# ecube_EIB_HS64_2xOmnetics_r1_0_30mm.net
KiCad netlist of a schematic drawn in EAGLE
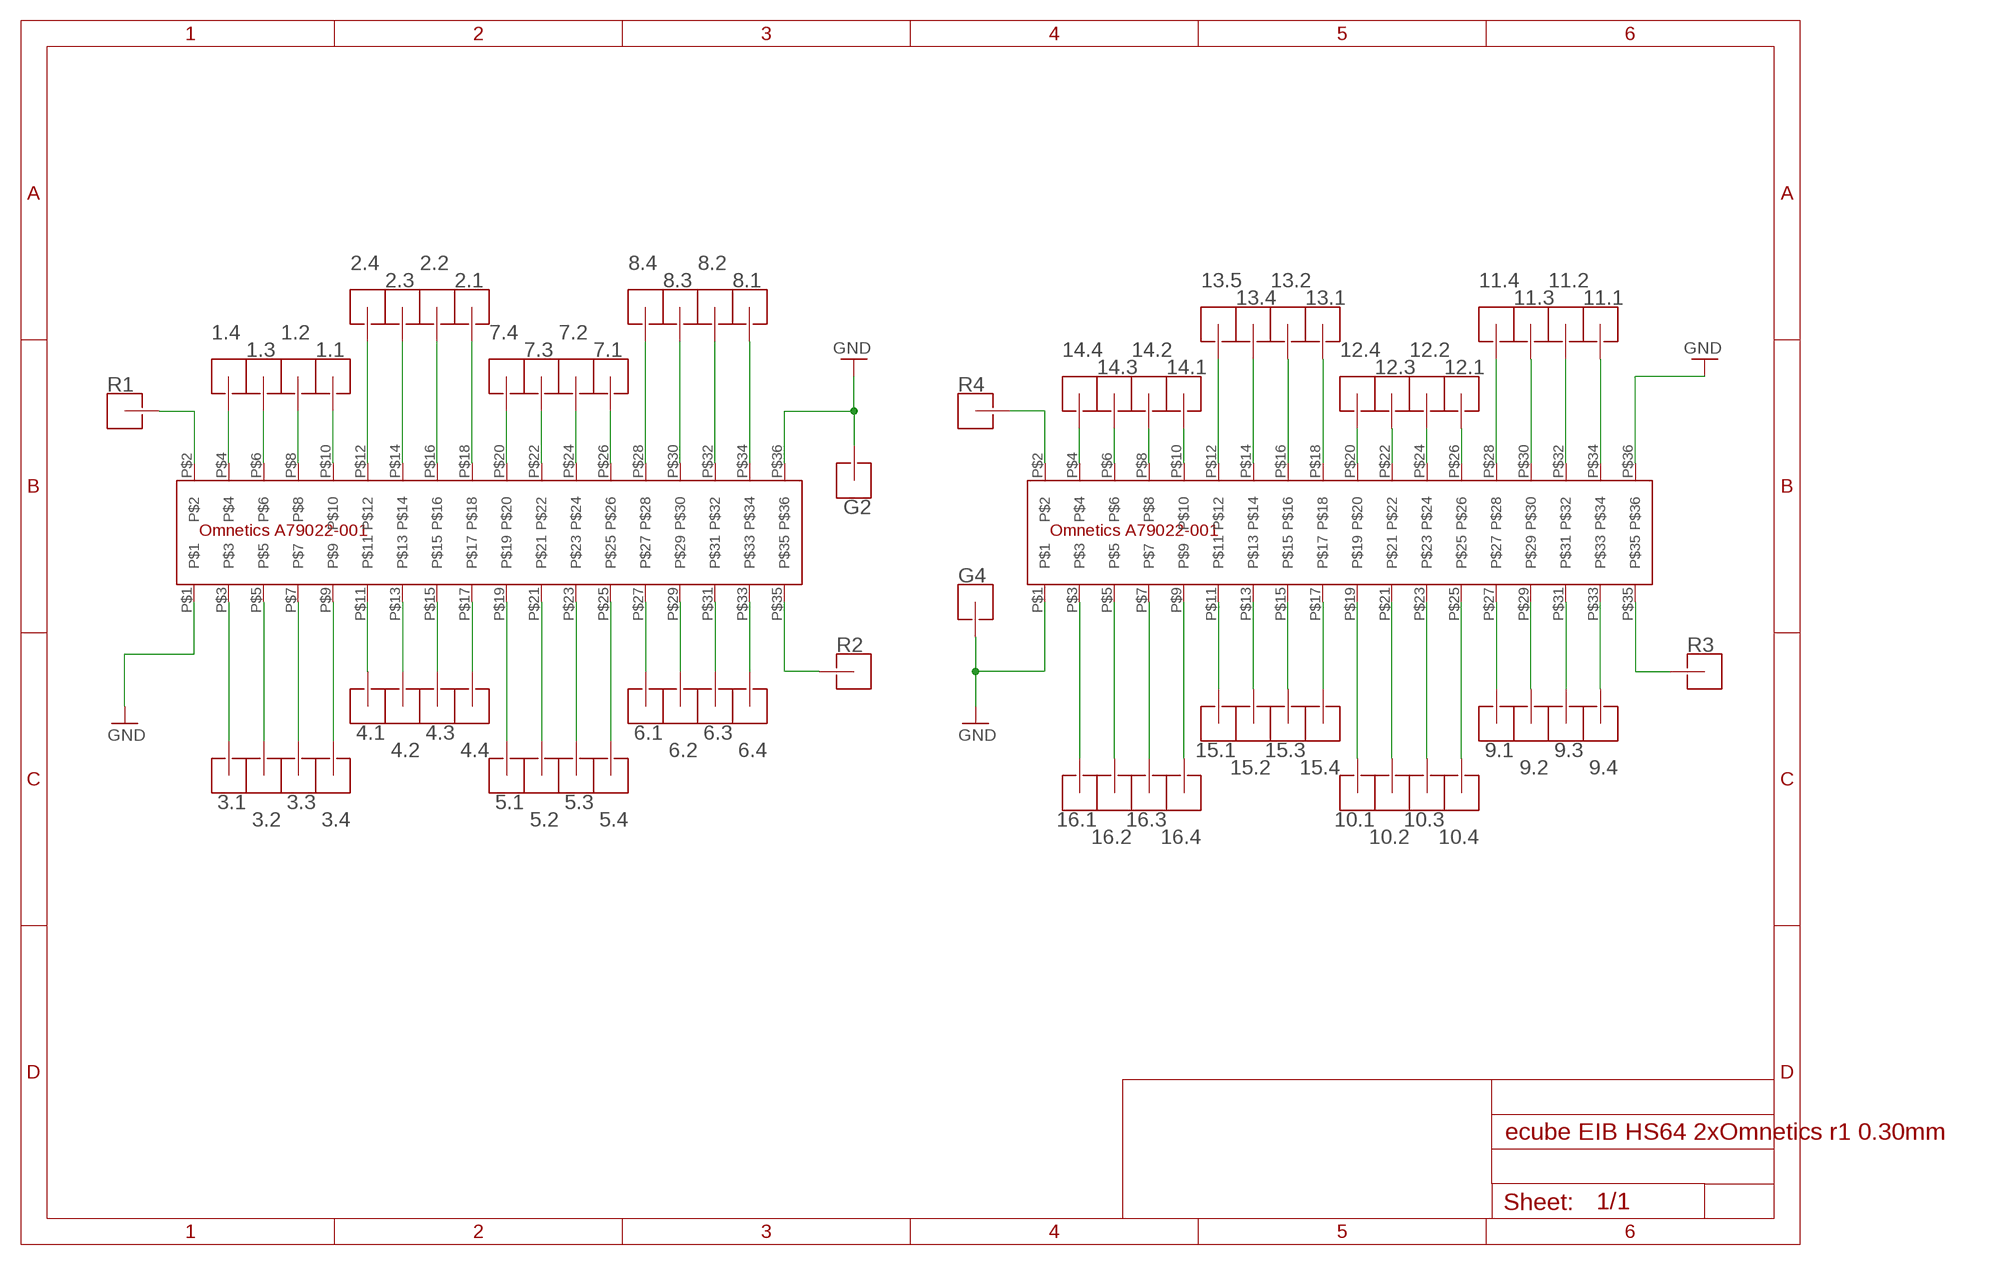
[diagram p0: schematic, sheet 1]

(export (version "E")
  (design (tool "Eeschema 10.0.6"))
  (components
    (comp (ref "1.1")
      (value "HOLE_S_G_PIN_V3")
      (footprint "eagle-import:SMALL_GOLD_PIN_V3")
      (libsource (lib "eagle-import") (part "HOLE_S_G_PIN_V3"))
    )
    (comp (ref "1.2")
      (value "HOLE_S_G_PIN_V3")
      (footprint "eagle-import:SMALL_GOLD_PIN_V3")
      (libsource (lib "eagle-import") (part "HOLE_S_G_PIN_V3"))
    )
    (comp (ref "1.3")
      (value "HOLE_S_G_PIN_V3")
      (footprint "eagle-import:SMALL_GOLD_PIN_V3")
      (libsource (lib "eagle-import") (part "HOLE_S_G_PIN_V3"))
    )
    (comp (ref "1.4")
      (value "HOLE_S_G_PIN_V3")
      (footprint "eagle-import:SMALL_GOLD_PIN_V3")
      (libsource (lib "eagle-import") (part "HOLE_S_G_PIN_V3"))
    )
    (comp (ref "2.1")
      (value "HOLE_S_G_PIN_V3")
      (footprint "eagle-import:SMALL_GOLD_PIN_V3")
      (libsource (lib "eagle-import") (part "HOLE_S_G_PIN_V3"))
    )
    (comp (ref "2.2")
      (value "HOLE_S_G_PIN_V3")
      (footprint "eagle-import:SMALL_GOLD_PIN_V3")
      (libsource (lib "eagle-import") (part "HOLE_S_G_PIN_V3"))
    )
    (comp (ref "2.3")
      (value "HOLE_S_G_PIN_V3")
      (footprint "eagle-import:SMALL_GOLD_PIN_V3")
      (libsource (lib "eagle-import") (part "HOLE_S_G_PIN_V3"))
    )
    (comp (ref "2.4")
      (value "HOLE_S_G_PIN_V3")
      (footprint "eagle-import:SMALL_GOLD_PIN_V3")
      (libsource (lib "eagle-import") (part "HOLE_S_G_PIN_V3"))
    )
    (comp (ref "3.1")
      (value "HOLE_S_G_PIN_V3")
      (footprint "eagle-import:SMALL_GOLD_PIN_V3")
      (libsource (lib "eagle-import") (part "HOLE_S_G_PIN_V3"))
    )
    (comp (ref "3.2")
      (value "HOLE_S_G_PIN_V3")
      (footprint "eagle-import:SMALL_GOLD_PIN_V3")
      (libsource (lib "eagle-import") (part "HOLE_S_G_PIN_V3"))
    )
    (comp (ref "3.3")
      (value "HOLE_S_G_PIN_V3")
      (footprint "eagle-import:SMALL_GOLD_PIN_V3")
      (libsource (lib "eagle-import") (part "HOLE_S_G_PIN_V3"))
    )
    (comp (ref "3.4")
      (value "HOLE_S_G_PIN_V3")
      (footprint "eagle-import:SMALL_GOLD_PIN_V3")
      (libsource (lib "eagle-import") (part "HOLE_S_G_PIN_V3"))
    )
    (comp (ref "4.1")
      (value "HOLE_S_G_PIN_V3")
      (footprint "eagle-import:SMALL_GOLD_PIN_V3")
      (libsource (lib "eagle-import") (part "HOLE_S_G_PIN_V3"))
    )
    (comp (ref "4.2")
      (value "HOLE_S_G_PIN_V3")
      (footprint "eagle-import:SMALL_GOLD_PIN_V3")
      (libsource (lib "eagle-import") (part "HOLE_S_G_PIN_V3"))
    )
    (comp (ref "4.3")
      (value "HOLE_S_G_PIN_V3")
      (footprint "eagle-import:SMALL_GOLD_PIN_V3")
      (libsource (lib "eagle-import") (part "HOLE_S_G_PIN_V3"))
    )
    (comp (ref "4.4")
      (value "HOLE_S_G_PIN_V3")
      (footprint "eagle-import:SMALL_GOLD_PIN_V3")
      (libsource (lib "eagle-import") (part "HOLE_S_G_PIN_V3"))
    )
    (comp (ref "5.1")
      (value "HOLE_S_G_PIN_V3")
      (footprint "eagle-import:SMALL_GOLD_PIN_V3")
      (libsource (lib "eagle-import") (part "HOLE_S_G_PIN_V3"))
    )
    (comp (ref "5.2")
      (value "HOLE_S_G_PIN_V3")
      (footprint "eagle-import:SMALL_GOLD_PIN_V3")
      (libsource (lib "eagle-import") (part "HOLE_S_G_PIN_V3"))
    )
    (comp (ref "5.3")
      (value "HOLE_S_G_PIN_V3")
      (footprint "eagle-import:SMALL_GOLD_PIN_V3")
      (libsource (lib "eagle-import") (part "HOLE_S_G_PIN_V3"))
    )
    (comp (ref "5.4")
      (value "HOLE_S_G_PIN_V3")
      (footprint "eagle-import:SMALL_GOLD_PIN_V3")
      (libsource (lib "eagle-import") (part "HOLE_S_G_PIN_V3"))
    )
    (comp (ref "6.1")
      (value "HOLE_S_G_PIN_V3")
      (footprint "eagle-import:SMALL_GOLD_PIN_V3")
      (libsource (lib "eagle-import") (part "HOLE_S_G_PIN_V3"))
    )
    (comp (ref "6.2")
      (value "HOLE_S_G_PIN_V3")
      (footprint "eagle-import:SMALL_GOLD_PIN_V3")
      (libsource (lib "eagle-import") (part "HOLE_S_G_PIN_V3"))
    )
    (comp (ref "6.3")
      (value "HOLE_S_G_PIN_V3")
      (footprint "eagle-import:SMALL_GOLD_PIN_V3")
      (libsource (lib "eagle-import") (part "HOLE_S_G_PIN_V3"))
    )
    (comp (ref "6.4")
      (value "HOLE_S_G_PIN_V3")
      (footprint "eagle-import:SMALL_GOLD_PIN_V3")
      (libsource (lib "eagle-import") (part "HOLE_S_G_PIN_V3"))
    )
    (comp (ref "7.1")
      (value "HOLE_S_G_PIN_V3")
      (footprint "eagle-import:SMALL_GOLD_PIN_V3")
      (libsource (lib "eagle-import") (part "HOLE_S_G_PIN_V3"))
    )
    (comp (ref "7.2")
      (value "HOLE_S_G_PIN_V3")
      (footprint "eagle-import:SMALL_GOLD_PIN_V3")
      (libsource (lib "eagle-import") (part "HOLE_S_G_PIN_V3"))
    )
    (comp (ref "7.3")
      (value "HOLE_S_G_PIN_V3")
      (footprint "eagle-import:SMALL_GOLD_PIN_V3")
      (libsource (lib "eagle-import") (part "HOLE_S_G_PIN_V3"))
    )
    (comp (ref "7.4")
      (value "HOLE_S_G_PIN_V3")
      (footprint "eagle-import:SMALL_GOLD_PIN_V3")
      (libsource (lib "eagle-import") (part "HOLE_S_G_PIN_V3"))
    )
    (comp (ref "8.1")
      (value "HOLE_S_G_PIN_V3")
      (footprint "eagle-import:SMALL_GOLD_PIN_V3")
      (libsource (lib "eagle-import") (part "HOLE_S_G_PIN_V3"))
    )
    (comp (ref "8.2")
      (value "HOLE_S_G_PIN_V3")
      (footprint "eagle-import:SMALL_GOLD_PIN_V3")
      (libsource (lib "eagle-import") (part "HOLE_S_G_PIN_V3"))
    )
    (comp (ref "8.3")
      (value "HOLE_S_G_PIN_V3")
      (footprint "eagle-import:SMALL_GOLD_PIN_V3")
      (libsource (lib "eagle-import") (part "HOLE_S_G_PIN_V3"))
    )
    (comp (ref "8.4")
      (value "HOLE_S_G_PIN_V3")
      (footprint "eagle-import:SMALL_GOLD_PIN_V3")
      (libsource (lib "eagle-import") (part "HOLE_S_G_PIN_V3"))
    )
    (comp (ref "9.1")
      (value "HOLE_S_G_PIN_V3")
      (footprint "eagle-import:SMALL_GOLD_PIN_V3")
      (libsource (lib "eagle-import") (part "HOLE_S_G_PIN_V3"))
    )
    (comp (ref "9.2")
      (value "HOLE_S_G_PIN_V3")
      (footprint "eagle-import:SMALL_GOLD_PIN_V3")
      (libsource (lib "eagle-import") (part "HOLE_S_G_PIN_V3"))
    )
    (comp (ref "9.3")
      (value "HOLE_S_G_PIN_V3")
      (footprint "eagle-import:SMALL_GOLD_PIN_V3")
      (libsource (lib "eagle-import") (part "HOLE_S_G_PIN_V3"))
    )
    (comp (ref "9.4")
      (value "HOLE_S_G_PIN_V3")
      (footprint "eagle-import:SMALL_GOLD_PIN_V3")
      (libsource (lib "eagle-import") (part "HOLE_S_G_PIN_V3"))
    )
    (comp (ref "10.1")
      (value "HOLE_S_G_PIN_V3")
      (footprint "eagle-import:SMALL_GOLD_PIN_V3")
      (libsource (lib "eagle-import") (part "HOLE_S_G_PIN_V3"))
    )
    (comp (ref "10.2")
      (value "HOLE_S_G_PIN_V3")
      (footprint "eagle-import:SMALL_GOLD_PIN_V3")
      (libsource (lib "eagle-import") (part "HOLE_S_G_PIN_V3"))
    )
    (comp (ref "10.3")
      (value "HOLE_S_G_PIN_V3")
      (footprint "eagle-import:SMALL_GOLD_PIN_V3")
      (libsource (lib "eagle-import") (part "HOLE_S_G_PIN_V3"))
    )
    (comp (ref "10.4")
      (value "HOLE_S_G_PIN_V3")
      (footprint "eagle-import:SMALL_GOLD_PIN_V3")
      (libsource (lib "eagle-import") (part "HOLE_S_G_PIN_V3"))
    )
    (comp (ref "11.1")
      (value "HOLE_S_G_PIN_V3")
      (footprint "eagle-import:SMALL_GOLD_PIN_V3")
      (libsource (lib "eagle-import") (part "HOLE_S_G_PIN_V3"))
    )
    (comp (ref "11.2")
      (value "HOLE_S_G_PIN_V3")
      (footprint "eagle-import:SMALL_GOLD_PIN_V3")
      (libsource (lib "eagle-import") (part "HOLE_S_G_PIN_V3"))
    )
    (comp (ref "11.3")
      (value "HOLE_S_G_PIN_V3")
      (footprint "eagle-import:SMALL_GOLD_PIN_V3")
      (libsource (lib "eagle-import") (part "HOLE_S_G_PIN_V3"))
    )
    (comp (ref "11.4")
      (value "HOLE_S_G_PIN_V3")
      (footprint "eagle-import:SMALL_GOLD_PIN_V3")
      (libsource (lib "eagle-import") (part "HOLE_S_G_PIN_V3"))
    )
    (comp (ref "12.1")
      (value "HOLE_S_G_PIN_V3")
      (footprint "eagle-import:SMALL_GOLD_PIN_V3")
      (libsource (lib "eagle-import") (part "HOLE_S_G_PIN_V3"))
    )
    (comp (ref "12.2")
      (value "HOLE_S_G_PIN_V3")
      (footprint "eagle-import:SMALL_GOLD_PIN_V3")
      (libsource (lib "eagle-import") (part "HOLE_S_G_PIN_V3"))
    )
    (comp (ref "12.3")
      (value "HOLE_S_G_PIN_V3")
      (footprint "eagle-import:SMALL_GOLD_PIN_V3")
      (libsource (lib "eagle-import") (part "HOLE_S_G_PIN_V3"))
    )
    (comp (ref "12.4")
      (value "HOLE_S_G_PIN_V3")
      (footprint "eagle-import:SMALL_GOLD_PIN_V3")
      (libsource (lib "eagle-import") (part "HOLE_S_G_PIN_V3"))
    )
    (comp (ref "13.1")
      (value "HOLE_S_G_PIN_V3")
      (footprint "eagle-import:SMALL_GOLD_PIN_V3")
      (libsource (lib "eagle-import") (part "HOLE_S_G_PIN_V3"))
    )
    (comp (ref "13.2")
      (value "HOLE_S_G_PIN_V3")
      (footprint "eagle-import:SMALL_GOLD_PIN_V3")
      (libsource (lib "eagle-import") (part "HOLE_S_G_PIN_V3"))
    )
    (comp (ref "13.4")
      (value "HOLE_S_G_PIN_V3")
      (footprint "eagle-import:SMALL_GOLD_PIN_V3")
      (libsource (lib "eagle-import") (part "HOLE_S_G_PIN_V3"))
    )
    (comp (ref "13.5")
      (value "HOLE_S_G_PIN_V3")
      (footprint "eagle-import:SMALL_GOLD_PIN_V3")
      (libsource (lib "eagle-import") (part "HOLE_S_G_PIN_V3"))
    )
    (comp (ref "14.1")
      (value "HOLE_S_G_PIN_V3")
      (footprint "eagle-import:SMALL_GOLD_PIN_V3")
      (libsource (lib "eagle-import") (part "HOLE_S_G_PIN_V3"))
    )
    (comp (ref "14.2")
      (value "HOLE_S_G_PIN_V3")
      (footprint "eagle-import:SMALL_GOLD_PIN_V3")
      (libsource (lib "eagle-import") (part "HOLE_S_G_PIN_V3"))
    )
    (comp (ref "14.3")
      (value "HOLE_S_G_PIN_V3")
      (footprint "eagle-import:SMALL_GOLD_PIN_V3")
      (libsource (lib "eagle-import") (part "HOLE_S_G_PIN_V3"))
    )
    (comp (ref "14.4")
      (value "HOLE_S_G_PIN_V3")
      (footprint "eagle-import:SMALL_GOLD_PIN_V3")
      (libsource (lib "eagle-import") (part "HOLE_S_G_PIN_V3"))
    )
    (comp (ref "15.1")
      (value "HOLE_S_G_PIN_V3")
      (footprint "eagle-import:SMALL_GOLD_PIN_V3")
      (libsource (lib "eagle-import") (part "HOLE_S_G_PIN_V3"))
    )
    (comp (ref "15.2")
      (value "HOLE_S_G_PIN_V3")
      (footprint "eagle-import:SMALL_GOLD_PIN_V3")
      (libsource (lib "eagle-import") (part "HOLE_S_G_PIN_V3"))
    )
    (comp (ref "15.3")
      (value "HOLE_S_G_PIN_V3")
      (footprint "eagle-import:SMALL_GOLD_PIN_V3")
      (libsource (lib "eagle-import") (part "HOLE_S_G_PIN_V3"))
    )
    (comp (ref "15.4")
      (value "HOLE_S_G_PIN_V3")
      (footprint "eagle-import:SMALL_GOLD_PIN_V3")
      (libsource (lib "eagle-import") (part "HOLE_S_G_PIN_V3"))
    )
    (comp (ref "16.1")
      (value "HOLE_S_G_PIN_V3")
      (footprint "eagle-import:SMALL_GOLD_PIN_V3")
      (libsource (lib "eagle-import") (part "HOLE_S_G_PIN_V3"))
    )
    (comp (ref "16.2")
      (value "HOLE_S_G_PIN_V3")
      (footprint "eagle-import:SMALL_GOLD_PIN_V3")
      (libsource (lib "eagle-import") (part "HOLE_S_G_PIN_V3"))
    )
    (comp (ref "16.3")
      (value "HOLE_S_G_PIN_V3")
      (footprint "eagle-import:SMALL_GOLD_PIN_V3")
      (libsource (lib "eagle-import") (part "HOLE_S_G_PIN_V3"))
    )
    (comp (ref "16.4")
      (value "HOLE_S_G_PIN_V3")
      (footprint "eagle-import:SMALL_GOLD_PIN_V3")
      (libsource (lib "eagle-import") (part "HOLE_S_G_PIN_V3"))
    )
    (comp (ref "G2")
      (value "HOLE_L_G_PIN_V1")
      (footprint "eagle-import:LARGE_GOLD_PIN_V1")
      (libsource (lib "eagle-import") (part "HOLE_L_G_PIN_V1"))
    )
    (comp (ref "G4")
      (value "HOLE_L_G_PIN_V1")
      (footprint "eagle-import:LARGE_GOLD_PIN_V1")
      (libsource (lib "eagle-import") (part "HOLE_L_G_PIN_V1"))
    )
    (comp (ref "R1")
      (value "HOLE_L_G_PIN_V1")
      (footprint "eagle-import:LARGE_GOLD_PIN_V1")
      (libsource (lib "eagle-import") (part "HOLE_L_G_PIN_V1"))
    )
    (comp (ref "R2")
      (value "HOLE_L_G_PIN_V1")
      (footprint "eagle-import:LARGE_GOLD_PIN_V1")
      (libsource (lib "eagle-import") (part "HOLE_L_G_PIN_V1"))
    )
    (comp (ref "R3")
      (value "HOLE_L_G_PIN_V1")
      (footprint "eagle-import:LARGE_GOLD_PIN_V1")
      (libsource (lib "eagle-import") (part "HOLE_L_G_PIN_V1"))
    )
    (comp (ref "R4")
      (value "HOLE_L_G_PIN_V1")
      (footprint "eagle-import:LARGE_GOLD_PIN_V1")
      (libsource (lib "eagle-import") (part "HOLE_L_G_PIN_V1"))
    )
    (comp (ref "U$1")
      (value "A79022-001")
      (footprint "eagle-import:A79022-001")
      (libsource (lib "eagle-import") (part "A79022-001"))
    )
    (comp (ref "U$2")
      (value "A79022-001")
      (footprint "eagle-import:A79022-001")
      (libsource (lib "eagle-import") (part "A79022-001"))
    )
  )
  (nets
    (net (code "1") (name "GND") (class "Default")
      (node (ref "G2") (pin "P$1") (pinfunction "P$1_P$1") (pintype "bidirectional"))
      (node (ref "G4") (pin "P$1") (pinfunction "P$1_P$1") (pintype "bidirectional"))
      (node (ref "U$1") (pin "P$1") (pinfunction "P$1_P$1") (pintype "bidirectional"))
      (node (ref "U$1") (pin "P$36") (pinfunction "P$36_P$36") (pintype "bidirectional"))
      (node (ref "U$2") (pin "P$1") (pinfunction "P$1_P$1") (pintype "bidirectional"))
      (node (ref "U$2") (pin "P$36") (pinfunction "P$36_P$36") (pintype "bidirectional"))
    )
    (net (code "2") (name "Net-(1.1-PadP$1)") (class "Default")
      (node (ref "1.1") (pin "P$1") (pinfunction "P$1_P$1") (pintype "bidirectional"))
      (node (ref "U$1") (pin "P$10") (pinfunction "P$10_P$10") (pintype "bidirectional"))
    )
    (net (code "3") (name "Net-(1.2-PadP$1)") (class "Default")
      (node (ref "1.2") (pin "P$1") (pinfunction "P$1_P$1") (pintype "bidirectional"))
      (node (ref "U$1") (pin "P$8") (pinfunction "P$8_P$8") (pintype "bidirectional"))
    )
    (net (code "4") (name "Net-(1.3-PadP$1)") (class "Default")
      (node (ref "1.3") (pin "P$1") (pinfunction "P$1_P$1") (pintype "bidirectional"))
      (node (ref "U$1") (pin "P$6") (pinfunction "P$6_P$6") (pintype "bidirectional"))
    )
    (net (code "5") (name "Net-(1.4-PadP$1)") (class "Default")
      (node (ref "1.4") (pin "P$1") (pinfunction "P$1_P$1") (pintype "bidirectional"))
      (node (ref "U$1") (pin "P$4") (pinfunction "P$4_P$4") (pintype "bidirectional"))
    )
    (net (code "6") (name "Net-(2.1-PadP$1)") (class "Default")
      (node (ref "2.1") (pin "P$1") (pinfunction "P$1_P$1") (pintype "bidirectional"))
      (node (ref "U$1") (pin "P$18") (pinfunction "P$18_P$18") (pintype "bidirectional"))
    )
    (net (code "7") (name "Net-(2.2-PadP$1)") (class "Default")
      (node (ref "2.2") (pin "P$1") (pinfunction "P$1_P$1") (pintype "bidirectional"))
      (node (ref "U$1") (pin "P$16") (pinfunction "P$16_P$16") (pintype "bidirectional"))
    )
    (net (code "8") (name "Net-(2.3-PadP$1)") (class "Default")
      (node (ref "2.3") (pin "P$1") (pinfunction "P$1_P$1") (pintype "bidirectional"))
      (node (ref "U$1") (pin "P$14") (pinfunction "P$14_P$14") (pintype "bidirectional"))
    )
    (net (code "9") (name "Net-(2.4-PadP$1)") (class "Default")
      (node (ref "2.4") (pin "P$1") (pinfunction "P$1_P$1") (pintype "bidirectional"))
      (node (ref "U$1") (pin "P$12") (pinfunction "P$12_P$12") (pintype "bidirectional"))
    )
    (net (code "10") (name "Net-(3.1-PadP$1)") (class "Default")
      (node (ref "3.1") (pin "P$1") (pinfunction "P$1_P$1") (pintype "bidirectional"))
      (node (ref "U$1") (pin "P$3") (pinfunction "P$3_P$3") (pintype "bidirectional"))
    )
    (net (code "11") (name "Net-(3.2-PadP$1)") (class "Default")
      (node (ref "3.2") (pin "P$1") (pinfunction "P$1_P$1") (pintype "bidirectional"))
      (node (ref "U$1") (pin "P$5") (pinfunction "P$5_P$5") (pintype "bidirectional"))
    )
    (net (code "12") (name "Net-(3.3-PadP$1)") (class "Default")
      (node (ref "3.3") (pin "P$1") (pinfunction "P$1_P$1") (pintype "bidirectional"))
      (node (ref "U$1") (pin "P$7") (pinfunction "P$7_P$7") (pintype "bidirectional"))
    )
    (net (code "13") (name "Net-(3.4-PadP$1)") (class "Default")
      (node (ref "3.4") (pin "P$1") (pinfunction "P$1_P$1") (pintype "bidirectional"))
      (node (ref "U$1") (pin "P$9") (pinfunction "P$9_P$9") (pintype "bidirectional"))
    )
    (net (code "14") (name "Net-(4.1-PadP$1)") (class "Default")
      (node (ref "4.1") (pin "P$1") (pinfunction "P$1_P$1") (pintype "bidirectional"))
      (node (ref "U$1") (pin "P$11") (pinfunction "P$11_P$11") (pintype "bidirectional"))
    )
    (net (code "15") (name "Net-(4.2-PadP$1)") (class "Default")
      (node (ref "4.2") (pin "P$1") (pinfunction "P$1_P$1") (pintype "bidirectional"))
      (node (ref "U$1") (pin "P$13") (pinfunction "P$13_P$13") (pintype "bidirectional"))
    )
    (net (code "16") (name "Net-(4.3-PadP$1)") (class "Default")
      (node (ref "4.3") (pin "P$1") (pinfunction "P$1_P$1") (pintype "bidirectional"))
      (node (ref "U$1") (pin "P$15") (pinfunction "P$15_P$15") (pintype "bidirectional"))
    )
    (net (code "17") (name "Net-(4.4-PadP$1)") (class "Default")
      (node (ref "4.4") (pin "P$1") (pinfunction "P$1_P$1") (pintype "bidirectional"))
      (node (ref "U$1") (pin "P$17") (pinfunction "P$17_P$17") (pintype "bidirectional"))
    )
    (net (code "18") (name "Net-(5.1-PadP$1)") (class "Default")
      (node (ref "5.1") (pin "P$1") (pinfunction "P$1_P$1") (pintype "bidirectional"))
      (node (ref "U$1") (pin "P$19") (pinfunction "P$19_P$19") (pintype "bidirectional"))
    )
    (net (code "19") (name "Net-(5.2-PadP$1)") (class "Default")
      (node (ref "5.2") (pin "P$1") (pinfunction "P$1_P$1") (pintype "bidirectional"))
      (node (ref "U$1") (pin "P$21") (pinfunction "P$21_P$21") (pintype "bidirectional"))
    )
    (net (code "20") (name "Net-(5.3-PadP$1)") (class "Default")
      (node (ref "5.3") (pin "P$1") (pinfunction "P$1_P$1") (pintype "bidirectional"))
      (node (ref "U$1") (pin "P$23") (pinfunction "P$23_P$23") (pintype "bidirectional"))
    )
    (net (code "21") (name "Net-(5.4-PadP$1)") (class "Default")
      (node (ref "5.4") (pin "P$1") (pinfunction "P$1_P$1") (pintype "bidirectional"))
      (node (ref "U$1") (pin "P$25") (pinfunction "P$25_P$25") (pintype "bidirectional"))
    )
    (net (code "22") (name "Net-(6.1-PadP$1)") (class "Default")
      (node (ref "6.1") (pin "P$1") (pinfunction "P$1_P$1") (pintype "bidirectional"))
      (node (ref "U$1") (pin "P$27") (pinfunction "P$27_P$27") (pintype "bidirectional"))
    )
    (net (code "23") (name "Net-(6.2-PadP$1)") (class "Default")
      (node (ref "6.2") (pin "P$1") (pinfunction "P$1_P$1") (pintype "bidirectional"))
      (node (ref "U$1") (pin "P$29") (pinfunction "P$29_P$29") (pintype "bidirectional"))
    )
    (net (code "24") (name "Net-(6.3-PadP$1)") (class "Default")
      (node (ref "6.3") (pin "P$1") (pinfunction "P$1_P$1") (pintype "bidirectional"))
      (node (ref "U$1") (pin "P$31") (pinfunction "P$31_P$31") (pintype "bidirectional"))
    )
    (net (code "25") (name "Net-(6.4-PadP$1)") (class "Default")
      (node (ref "6.4") (pin "P$1") (pinfunction "P$1_P$1") (pintype "bidirectional"))
      (node (ref "U$1") (pin "P$33") (pinfunction "P$33_P$33") (pintype "bidirectional"))
    )
    (net (code "26") (name "Net-(7.1-PadP$1)") (class "Default")
      (node (ref "7.1") (pin "P$1") (pinfunction "P$1_P$1") (pintype "bidirectional"))
      (node (ref "U$1") (pin "P$26") (pinfunction "P$26_P$26") (pintype "bidirectional"))
    )
    (net (code "27") (name "Net-(7.2-PadP$1)") (class "Default")
      (node (ref "7.2") (pin "P$1") (pinfunction "P$1_P$1") (pintype "bidirectional"))
      (node (ref "U$1") (pin "P$24") (pinfunction "P$24_P$24") (pintype "bidirectional"))
    )
    (net (code "28") (name "Net-(7.3-PadP$1)") (class "Default")
      (node (ref "7.3") (pin "P$1") (pinfunction "P$1_P$1") (pintype "bidirectional"))
      (node (ref "U$1") (pin "P$22") (pinfunction "P$22_P$22") (pintype "bidirectional"))
    )
    (net (code "29") (name "Net-(7.4-PadP$1)") (class "Default")
      (node (ref "7.4") (pin "P$1") (pinfunction "P$1_P$1") (pintype "bidirectional"))
      (node (ref "U$1") (pin "P$20") (pinfunction "P$20_P$20") (pintype "bidirectional"))
    )
    (net (code "30") (name "Net-(8.1-PadP$1)") (class "Default")
      (node (ref "8.1") (pin "P$1") (pinfunction "P$1_P$1") (pintype "bidirectional"))
      (node (ref "U$1") (pin "P$34") (pinfunction "P$34_P$34") (pintype "bidirectional"))
    )
    (net (code "31") (name "Net-(8.2-PadP$1)") (class "Default")
      (node (ref "8.2") (pin "P$1") (pinfunction "P$1_P$1") (pintype "bidirectional"))
      (node (ref "U$1") (pin "P$32") (pinfunction "P$32_P$32") (pintype "bidirectional"))
    )
    (net (code "32") (name "Net-(8.3-PadP$1)") (class "Default")
      (node (ref "8.3") (pin "P$1") (pinfunction "P$1_P$1") (pintype "bidirectional"))
      (node (ref "U$1") (pin "P$30") (pinfunction "P$30_P$30") (pintype "bidirectional"))
    )
    (net (code "33") (name "Net-(8.4-PadP$1)") (class "Default")
      (node (ref "8.4") (pin "P$1") (pinfunction "P$1_P$1") (pintype "bidirectional"))
      (node (ref "U$1") (pin "P$28") (pinfunction "P$28_P$28") (pintype "bidirectional"))
    )
    (net (code "34") (name "Net-(9.1-PadP$1)") (class "Default")
      (node (ref "9.1") (pin "P$1") (pinfunction "P$1_P$1") (pintype "bidirectional"))
      (node (ref "U$2") (pin "P$27") (pinfunction "P$27_P$27") (pintype "bidirectional"))
    )
    (net (code "35") (name "Net-(9.2-PadP$1)") (class "Default")
      (node (ref "9.2") (pin "P$1") (pinfunction "P$1_P$1") (pintype "bidirectional"))
      (node (ref "U$2") (pin "P$29") (pinfunction "P$29_P$29") (pintype "bidirectional"))
    )
    (net (code "36") (name "Net-(9.3-PadP$1)") (class "Default")
      (node (ref "9.3") (pin "P$1") (pinfunction "P$1_P$1") (pintype "bidirectional"))
      (node (ref "U$2") (pin "P$31") (pinfunction "P$31_P$31") (pintype "bidirectional"))
    )
    (net (code "37") (name "Net-(9.4-PadP$1)") (class "Default")
      (node (ref "9.4") (pin "P$1") (pinfunction "P$1_P$1") (pintype "bidirectional"))
      (node (ref "U$2") (pin "P$33") (pinfunction "P$33_P$33") (pintype "bidirectional"))
    )
    (net (code "38") (name "Net-(10.1-PadP$1)") (class "Default")
      (node (ref "10.1") (pin "P$1") (pinfunction "P$1_P$1") (pintype "bidirectional"))
      (node (ref "U$2") (pin "P$19") (pinfunction "P$19_P$19") (pintype "bidirectional"))
    )
    (net (code "39") (name "Net-(10.2-PadP$1)") (class "Default")
      (node (ref "10.2") (pin "P$1") (pinfunction "P$1_P$1") (pintype "bidirectional"))
      (node (ref "U$2") (pin "P$21") (pinfunction "P$21_P$21") (pintype "bidirectional"))
    )
    (net (code "40") (name "Net-(10.3-PadP$1)") (class "Default")
      (node (ref "10.3") (pin "P$1") (pinfunction "P$1_P$1") (pintype "bidirectional"))
      (node (ref "U$2") (pin "P$23") (pinfunction "P$23_P$23") (pintype "bidirectional"))
    )
    (net (code "41") (name "Net-(10.4-PadP$1)") (class "Default")
      (node (ref "10.4") (pin "P$1") (pinfunction "P$1_P$1") (pintype "bidirectional"))
      (node (ref "U$2") (pin "P$25") (pinfunction "P$25_P$25") (pintype "bidirectional"))
    )
    (net (code "42") (name "Net-(11.1-PadP$1)") (class "Default")
      (node (ref "11.1") (pin "P$1") (pinfunction "P$1_P$1") (pintype "bidirectional"))
      (node (ref "U$2") (pin "P$34") (pinfunction "P$34_P$34") (pintype "bidirectional"))
    )
    (net (code "43") (name "Net-(11.2-PadP$1)") (class "Default")
      (node (ref "11.2") (pin "P$1") (pinfunction "P$1_P$1") (pintype "bidirectional"))
      (node (ref "U$2") (pin "P$32") (pinfunction "P$32_P$32") (pintype "bidirectional"))
    )
    (net (code "44") (name "Net-(11.3-PadP$1)") (class "Default")
      (node (ref "11.3") (pin "P$1") (pinfunction "P$1_P$1") (pintype "bidirectional"))
      (node (ref "U$2") (pin "P$30") (pinfunction "P$30_P$30") (pintype "bidirectional"))
    )
    (net (code "45") (name "Net-(11.4-PadP$1)") (class "Default")
      (node (ref "11.4") (pin "P$1") (pinfunction "P$1_P$1") (pintype "bidirectional"))
      (node (ref "U$2") (pin "P$28") (pinfunction "P$28_P$28") (pintype "bidirectional"))
    )
    (net (code "46") (name "Net-(12.1-PadP$1)") (class "Default")
      (node (ref "12.1") (pin "P$1") (pinfunction "P$1_P$1") (pintype "bidirectional"))
      (node (ref "U$2") (pin "P$26") (pinfunction "P$26_P$26") (pintype "bidirectional"))
    )
    (net (code "47") (name "Net-(12.2-PadP$1)") (class "Default")
      (node (ref "12.2") (pin "P$1") (pinfunction "P$1_P$1") (pintype "bidirectional"))
      (node (ref "U$2") (pin "P$24") (pinfunction "P$24_P$24") (pintype "bidirectional"))
    )
    (net (code "48") (name "Net-(12.3-PadP$1)") (class "Default")
      (node (ref "12.3") (pin "P$1") (pinfunction "P$1_P$1") (pintype "bidirectional"))
      (node (ref "U$2") (pin "P$22") (pinfunction "P$22_P$22") (pintype "bidirectional"))
    )
    (net (code "49") (name "Net-(12.4-PadP$1)") (class "Default")
      (node (ref "12.4") (pin "P$1") (pinfunction "P$1_P$1") (pintype "bidirectional"))
      (node (ref "U$2") (pin "P$20") (pinfunction "P$20_P$20") (pintype "bidirectional"))
    )
    (net (code "50") (name "Net-(13.1-PadP$1)") (class "Default")
      (node (ref "13.1") (pin "P$1") (pinfunction "P$1_P$1") (pintype "bidirectional"))
      (node (ref "U$2") (pin "P$18") (pinfunction "P$18_P$18") (pintype "bidirectional"))
    )
    (net (code "51") (name "Net-(13.2-PadP$1)") (class "Default")
      (node (ref "13.2") (pin "P$1") (pinfunction "P$1_P$1") (pintype "bidirectional"))
      (node (ref "U$2") (pin "P$16") (pinfunction "P$16_P$16") (pintype "bidirectional"))
    )
    (net (code "52") (name "Net-(13.4-PadP$1)") (class "Default")
      (node (ref "13.4") (pin "P$1") (pinfunction "P$1_P$1") (pintype "bidirectional"))
      (node (ref "U$2") (pin "P$14") (pinfunction "P$14_P$14") (pintype "bidirectional"))
    )
    (net (code "53") (name "Net-(13.5-PadP$1)") (class "Default")
      (node (ref "13.5") (pin "P$1") (pinfunction "P$1_P$1") (pintype "bidirectional"))
      (node (ref "U$2") (pin "P$12") (pinfunction "P$12_P$12") (pintype "bidirectional"))
    )
    (net (code "54") (name "Net-(14.1-PadP$1)") (class "Default")
      (node (ref "14.1") (pin "P$1") (pinfunction "P$1_P$1") (pintype "bidirectional"))
      (node (ref "U$2") (pin "P$10") (pinfunction "P$10_P$10") (pintype "bidirectional"))
    )
    (net (code "55") (name "Net-(14.2-PadP$1)") (class "Default")
      (node (ref "14.2") (pin "P$1") (pinfunction "P$1_P$1") (pintype "bidirectional"))
      (node (ref "U$2") (pin "P$8") (pinfunction "P$8_P$8") (pintype "bidirectional"))
    )
    (net (code "56") (name "Net-(14.3-PadP$1)") (class "Default")
      (node (ref "14.3") (pin "P$1") (pinfunction "P$1_P$1") (pintype "bidirectional"))
      (node (ref "U$2") (pin "P$6") (pinfunction "P$6_P$6") (pintype "bidirectional"))
    )
    (net (code "57") (name "Net-(14.4-PadP$1)") (class "Default")
      (node (ref "14.4") (pin "P$1") (pinfunction "P$1_P$1") (pintype "bidirectional"))
      (node (ref "U$2") (pin "P$4") (pinfunction "P$4_P$4") (pintype "bidirectional"))
    )
    (net (code "58") (name "Net-(15.1-PadP$1)") (class "Default")
      (node (ref "15.1") (pin "P$1") (pinfunction "P$1_P$1") (pintype "bidirectional"))
      (node (ref "U$2") (pin "P$11") (pinfunction "P$11_P$11") (pintype "bidirectional"))
    )
    (net (code "59") (name "Net-(15.2-PadP$1)") (class "Default")
      (node (ref "15.2") (pin "P$1") (pinfunction "P$1_P$1") (pintype "bidirectional"))
      (node (ref "U$2") (pin "P$13") (pinfunction "P$13_P$13") (pintype "bidirectional"))
    )
    (net (code "60") (name "Net-(15.3-PadP$1)") (class "Default")
      (node (ref "15.3") (pin "P$1") (pinfunction "P$1_P$1") (pintype "bidirectional"))
      (node (ref "U$2") (pin "P$15") (pinfunction "P$15_P$15") (pintype "bidirectional"))
    )
    (net (code "61") (name "Net-(15.4-PadP$1)") (class "Default")
      (node (ref "15.4") (pin "P$1") (pinfunction "P$1_P$1") (pintype "bidirectional"))
      (node (ref "U$2") (pin "P$17") (pinfunction "P$17_P$17") (pintype "bidirectional"))
    )
    (net (code "62") (name "Net-(16.1-PadP$1)") (class "Default")
      (node (ref "16.1") (pin "P$1") (pinfunction "P$1_P$1") (pintype "bidirectional"))
      (node (ref "U$2") (pin "P$3") (pinfunction "P$3_P$3") (pintype "bidirectional"))
    )
    (net (code "63") (name "Net-(16.2-PadP$1)") (class "Default")
      (node (ref "16.2") (pin "P$1") (pinfunction "P$1_P$1") (pintype "bidirectional"))
      (node (ref "U$2") (pin "P$5") (pinfunction "P$5_P$5") (pintype "bidirectional"))
    )
    (net (code "64") (name "Net-(16.3-PadP$1)") (class "Default")
      (node (ref "16.3") (pin "P$1") (pinfunction "P$1_P$1") (pintype "bidirectional"))
      (node (ref "U$2") (pin "P$7") (pinfunction "P$7_P$7") (pintype "bidirectional"))
    )
    (net (code "65") (name "Net-(16.4-PadP$1)") (class "Default")
      (node (ref "16.4") (pin "P$1") (pinfunction "P$1_P$1") (pintype "bidirectional"))
      (node (ref "U$2") (pin "P$9") (pinfunction "P$9_P$9") (pintype "bidirectional"))
    )
    (net (code "66") (name "Net-(R1-PadP$1)") (class "Default")
      (node (ref "R1") (pin "P$1") (pinfunction "P$1_P$1") (pintype "bidirectional"))
      (node (ref "U$1") (pin "P$2") (pinfunction "P$2_P$2") (pintype "bidirectional"))
    )
    (net (code "67") (name "Net-(R2-PadP$1)") (class "Default")
      (node (ref "R2") (pin "P$1") (pinfunction "P$1_P$1") (pintype "bidirectional"))
      (node (ref "U$1") (pin "P$35") (pinfunction "P$35_P$35") (pintype "bidirectional"))
    )
    (net (code "68") (name "Net-(R3-PadP$1)") (class "Default")
      (node (ref "R3") (pin "P$1") (pinfunction "P$1_P$1") (pintype "bidirectional"))
      (node (ref "U$2") (pin "P$35") (pinfunction "P$35_P$35") (pintype "bidirectional"))
    )
    (net (code "69") (name "Net-(R4-PadP$1)") (class "Default")
      (node (ref "R4") (pin "P$1") (pinfunction "P$1_P$1") (pintype "bidirectional"))
      (node (ref "U$2") (pin "P$2") (pinfunction "P$2_P$2") (pintype "bidirectional"))
    )
  )
)
